# Sheet1.net
KiCad netlist of a schematic drawn in Altium Designer
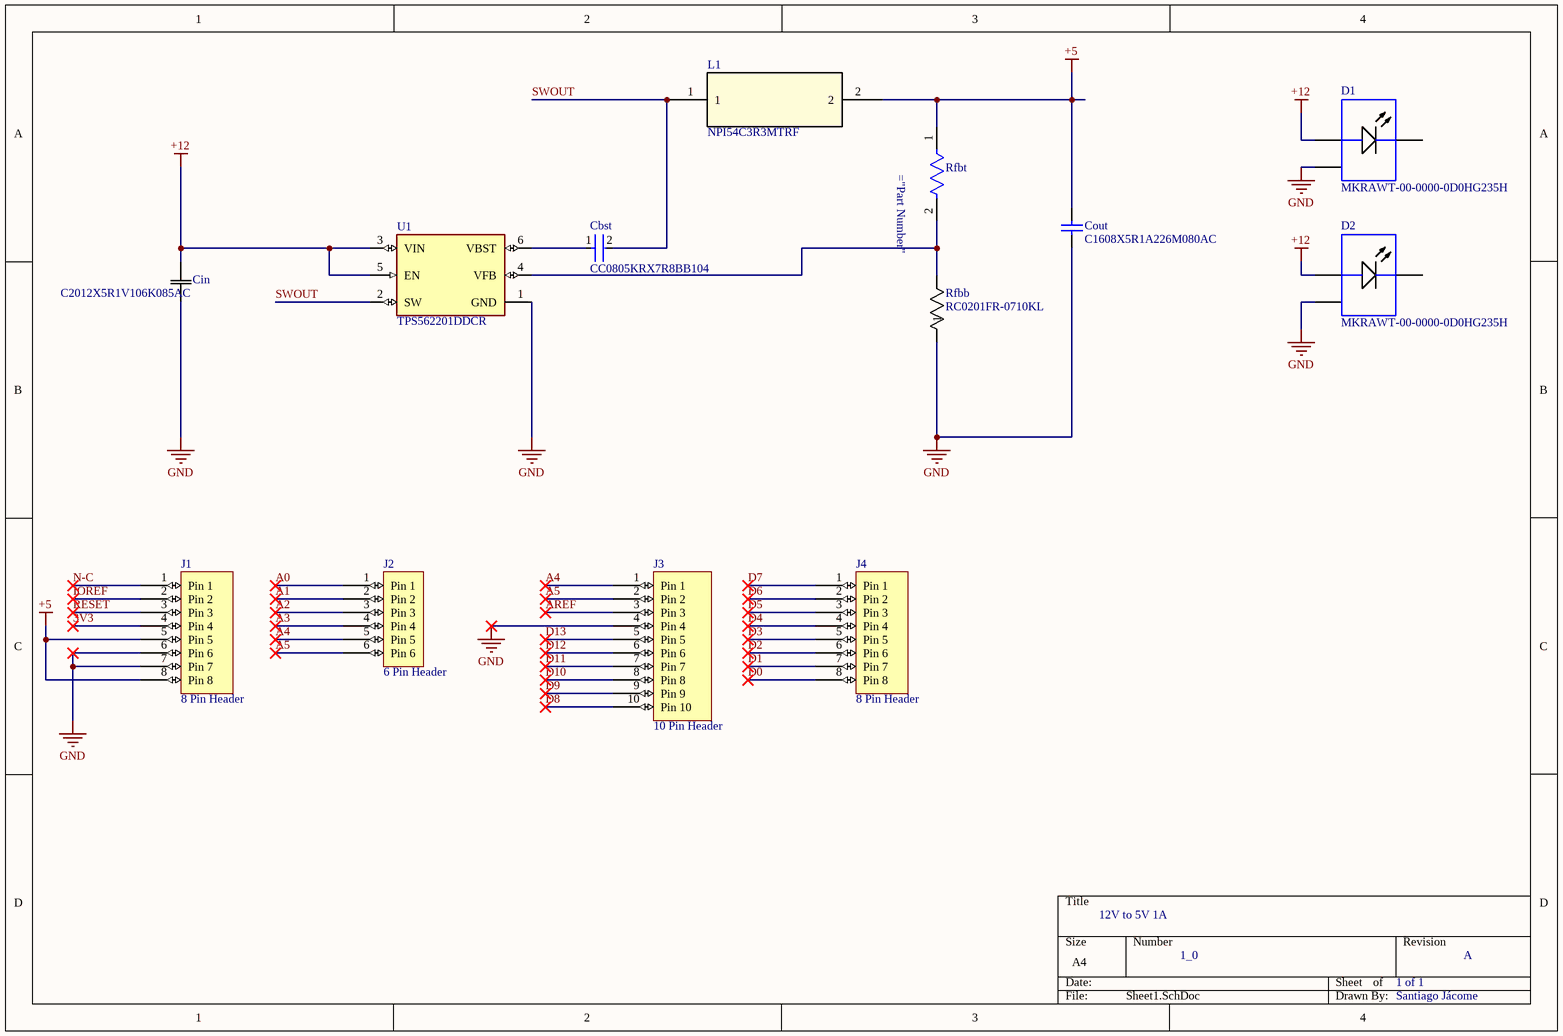
[diagram p0: Sheet1.SchDoc]

(export (version "E")
  (design (tool "Eeschema 10.0.6"))
  (components
    (comp (ref "Cbst")
      (value "CC0805KRX7R8BB104")
      (footprint "FP-CC0805-0_85-MFG")
      (description "CAP CER 0.1UF 25V X7R 0805")
      (fields (field (name "TOLERANCE") "0.1") (field (name "MANUFACTURER") "Yageo"))
      (libsource (lib "Altium Content Vault") (part "11868f565c42a9108669ba33697ecf6"))
    )
    (comp (ref "Cin")
      (value "C2012X5R1V106K085AC")
      (footprint "C2012X5R1V106K085AC:CAP_2012_TDK-M")
      (description "10uf")
      (libsource (lib "C2012X5R1V106K085AC") (part "C2012X5R1V106K085AC"))
    )
    (comp (ref "Cout")
      (value "C1608X5R1A226M080AC")
      (footprint "CAPC1608X100X20ML10")
      (description "Chip Capacitor, 22 uF, +/- 20%, 10 V, -55 to 85 degC, 0603 (1608 Metric), RoHS, Tape and Reel")
      (fields (field (name "MANUFACTURER") "TDK") (field (name "TOLERANCE") "±20%"))
      (libsource (lib "Altium Content Vault") (part "CAP-NP-2"))
    )
    (comp (ref "D1")
      (value "MKRAWT-00-0000-0D0HG235H")
      (footprint "CREE-MK-R-2_V")
      (description "LED, White, 12 V, 2-Pin SMD, RoHS, Tape and Reel")
      (libsource (lib "Altium Content Vault") (part "LED_WHITE-3"))
    )
    (comp (ref "D2")
      (value "MKRAWT-00-0000-0D0HG235H")
      (footprint "CREE-MK-R-2_V")
      (description "LED, White, 12 V, 2-Pin SMD, RoHS, Tape and Reel")
      (libsource (lib "Altium Content Vault") (part "LED_WHITE-3"))
    )
    (comp (ref "J1")
      (value "8 Pin Header")
      (footprint "8 Pin Header-Footprint-1")
      (description "Arduino 8 Pin Header: 30 mils hole diameter, 60 mils pad diameter, 100 mils pin-to-pin")
      (libsource (lib "Altium Certification") (part "8 Pin Header-Symbol-1"))
    )
    (comp (ref "J2")
      (value "6 Pin Header")
      (footprint "6 Pin Header-Footprint-1")
      (description "Arduino 6 Pin Header: 30 mils hole diameter, 60 mils pad diameter, 100 mils pin-to-pin")
      (libsource (lib "Altium Certification") (part "6 Pin Header-Symbol-1"))
    )
    (comp (ref "J3")
      (value "10 Pin Header")
      (footprint "10 Pin Header-Footprint-1")
      (description "Arduino 10 Pin Header: 30 mils hole diameter, 60 mils pad diameter, 100 mils pin-to-pin")
      (libsource (lib "Altium Certification") (part "10 Pin Header-Symbol-1"))
    )
    (comp (ref "J4")
      (value "8 Pin Header")
      (footprint "8 Pin Header-Footprint-1")
      (description "Arduino 8 Pin Header: 30 mils hole diameter, 60 mils pad diameter, 100 mils pin-to-pin")
      (libsource (lib "Altium Certification") (part "8 Pin Header-Symbol-1"))
    )
    (comp (ref "L1")
      (value "NPI54C3R3MTRF")
      (footprint "NPI54C3R3MTRF_NIC")
      (description "No Description Available")
      (libsource (lib "NPI54C3R3MTRF") (part "NPI54C3R3MTRF"))
    )
    (comp (ref "Rfbb")
      (value "RC0201FR-0710KL")
      (footprint "YAG_R0201_YAG-L")
      (description "10k Ohms")
      (libsource (lib "RC0201FR-0710KL") (part "RC0201FR-0710KL"))
    )
    (comp (ref "Rfbt")
      (value "RC0201FR-0756K2L")
      (footprint "Yageo_RC0201_MFG")
      (description "56.2k Ohms")
      (libsource (lib "Res_Yageo_RC0201FR-0756K2L_eec") (part "RC0201FR-0756K2L"))
    )
    (comp (ref "U1")
      (value "TPS562201DDCR")
      (footprint "FP-DDC0006A-IPC_C")
      (description "IC REG BUCK ADJ 2A TSOT23-6")
      (libsource (lib "Altium Content Vault") (part "957e164956730ea4bf6293280af19fc"))
    )
  )
  (nets
    (net (code "1") (name "+5") (class "Default")
      (node (ref "Cout") (pin "2") (pinfunction "2_2") (pintype "passive"))
      (node (ref "J1") (pin "5") (pinfunction "Pin_5_5") (pintype "bidirectional"))
      (node (ref "J1") (pin "8") (pinfunction "Pin_8_8") (pintype "bidirectional"))
      (node (ref "L1") (pin "2") (pinfunction "2_2") (pintype "passive"))
      (node (ref "Rfbt") (pin "1") (pinfunction "1_1") (pintype "passive"))
    )
    (net (code "2") (name "+12") (class "Default")
      (node (ref "Cin") (pin "2") (pinfunction "2_2") (pintype "passive"))
      (node (ref "D1") (pin "1") (pinfunction "A_1") (pintype "passive"))
      (node (ref "D2") (pin "1") (pinfunction "A_1") (pintype "passive"))
      (node (ref "U1") (pin "3") (pinfunction "VIN_3") (pintype "bidirectional"))
      (node (ref "U1") (pin "5") (pinfunction "EN_5") (pintype "input"))
    )
    (net (code "3") (name "/3V3") (class "Default")
      (node (ref "J1") (pin "4") (pinfunction "Pin_4_4") (pintype "bidirectional+no_connect"))
    )
    (net (code "4") (name "/A0") (class "Default")
      (node (ref "J2") (pin "1") (pinfunction "Pin_1_1") (pintype "bidirectional+no_connect"))
    )
    (net (code "5") (name "/A1") (class "Default")
      (node (ref "J2") (pin "2") (pinfunction "Pin_2_2") (pintype "bidirectional+no_connect"))
    )
    (net (code "6") (name "/A2") (class "Default")
      (node (ref "J2") (pin "3") (pinfunction "Pin_3_3") (pintype "bidirectional+no_connect"))
    )
    (net (code "7") (name "/A3") (class "Default")
      (node (ref "J2") (pin "4") (pinfunction "Pin_4_4") (pintype "bidirectional+no_connect"))
    )
    (net (code "8") (name "/A4") (class "Default")
      (node (ref "J2") (pin "5") (pinfunction "Pin_5_5") (pintype "bidirectional"))
      (node (ref "J3") (pin "1") (pinfunction "Pin_1_1") (pintype "bidirectional"))
    )
    (net (code "9") (name "/A5") (class "Default")
      (node (ref "J2") (pin "6") (pinfunction "Pin_6_6") (pintype "bidirectional"))
      (node (ref "J3") (pin "2") (pinfunction "Pin_2_2") (pintype "bidirectional"))
    )
    (net (code "10") (name "/AREF") (class "Default")
      (node (ref "J3") (pin "3") (pinfunction "Pin_3_3") (pintype "bidirectional+no_connect"))
    )
    (net (code "11") (name "/D0") (class "Default")
      (node (ref "J4") (pin "8") (pinfunction "Pin_8_8") (pintype "bidirectional+no_connect"))
    )
    (net (code "12") (name "/D1") (class "Default")
      (node (ref "J4") (pin "7") (pinfunction "Pin_7_7") (pintype "bidirectional+no_connect"))
    )
    (net (code "13") (name "/D2") (class "Default")
      (node (ref "J4") (pin "6") (pinfunction "Pin_6_6") (pintype "bidirectional+no_connect"))
    )
    (net (code "14") (name "/D3") (class "Default")
      (node (ref "J4") (pin "5") (pinfunction "Pin_5_5") (pintype "bidirectional+no_connect"))
    )
    (net (code "15") (name "/D4") (class "Default")
      (node (ref "J4") (pin "4") (pinfunction "Pin_4_4") (pintype "bidirectional+no_connect"))
    )
    (net (code "16") (name "/D5") (class "Default")
      (node (ref "J4") (pin "3") (pinfunction "Pin_3_3") (pintype "bidirectional+no_connect"))
    )
    (net (code "17") (name "/D6") (class "Default")
      (node (ref "J4") (pin "2") (pinfunction "Pin_2_2") (pintype "bidirectional+no_connect"))
    )
    (net (code "18") (name "/D7") (class "Default")
      (node (ref "J4") (pin "1") (pinfunction "Pin_1_1") (pintype "bidirectional+no_connect"))
    )
    (net (code "19") (name "/D8") (class "Default")
      (node (ref "J3") (pin "10") (pinfunction "Pin_10_10") (pintype "bidirectional+no_connect"))
    )
    (net (code "20") (name "/D9") (class "Default")
      (node (ref "J3") (pin "9") (pinfunction "Pin_9_9") (pintype "bidirectional+no_connect"))
    )
    (net (code "21") (name "/D10") (class "Default")
      (node (ref "J3") (pin "8") (pinfunction "Pin_8_8") (pintype "bidirectional+no_connect"))
    )
    (net (code "22") (name "/D11") (class "Default")
      (node (ref "J3") (pin "7") (pinfunction "Pin_7_7") (pintype "bidirectional+no_connect"))
    )
    (net (code "23") (name "/D12") (class "Default")
      (node (ref "J3") (pin "6") (pinfunction "Pin_6_6") (pintype "bidirectional+no_connect"))
    )
    (net (code "24") (name "/D13") (class "Default")
      (node (ref "J3") (pin "5") (pinfunction "Pin_5_5") (pintype "bidirectional+no_connect"))
    )
    (net (code "25") (name "/IOREF") (class "Default")
      (node (ref "J1") (pin "2") (pinfunction "Pin_2_2") (pintype "bidirectional+no_connect"))
    )
    (net (code "26") (name "/N-C") (class "Default")
      (node (ref "J1") (pin "1") (pinfunction "Pin_1_1") (pintype "bidirectional+no_connect"))
    )
    (net (code "27") (name "/RESET") (class "Default")
      (node (ref "J1") (pin "3") (pinfunction "Pin_3_3") (pintype "bidirectional+no_connect"))
    )
    (net (code "28") (name "/SWOUT") (class "Default")
      (node (ref "Cbst") (pin "2") (pinfunction "2_2") (pintype "passive"))
      (node (ref "L1") (pin "1") (pinfunction "1_1") (pintype "passive"))
      (node (ref "U1") (pin "2") (pinfunction "SW_2") (pintype "bidirectional"))
    )
    (net (code "29") (name "GND") (class "Default")
      (node (ref "Cin") (pin "1") (pinfunction "1_1") (pintype "passive"))
      (node (ref "Cout") (pin "1") (pinfunction "1_1") (pintype "passive"))
      (node (ref "D1") (pin "3") (pinfunction "EP_3") (pintype "passive"))
      (node (ref "D2") (pin "3") (pinfunction "EP_3") (pintype "passive"))
      (node (ref "J1") (pin "6") (pinfunction "Pin_6_6") (pintype "bidirectional"))
      (node (ref "J1") (pin "7") (pinfunction "Pin_7_7") (pintype "bidirectional"))
      (node (ref "J3") (pin "4") (pinfunction "Pin_4_4") (pintype "bidirectional"))
      (node (ref "Rfbb") (pin "1") (pinfunction "1_1") (pintype "passive"))
      (node (ref "U1") (pin "1") (pinfunction "GND_1") (pintype "power_in"))
    )
    (net (code "30") (name "Net-(U1-VBST)") (class "Default")
      (node (ref "Cbst") (pin "1") (pinfunction "1_1") (pintype "passive"))
      (node (ref "U1") (pin "6") (pinfunction "VBST_6") (pintype "bidirectional"))
    )
    (net (code "31") (name "Net-(U1-VFB)") (class "Default")
      (node (ref "Rfbb") (pin "2") (pinfunction "2_2") (pintype "passive"))
      (node (ref "Rfbt") (pin "2") (pinfunction "2_2") (pintype "passive"))
      (node (ref "U1") (pin "4") (pinfunction "VFB_4") (pintype "bidirectional"))
    )
    (net (code "32") (name "unconnected-(D1-K-Pad2)") (class "Default")
      (node (ref "D1") (pin "2") (pinfunction "K_2") (pintype "passive"))
    )
    (net (code "33") (name "unconnected-(D2-K-Pad2)") (class "Default")
      (node (ref "D2") (pin "2") (pinfunction "K_2") (pintype "passive"))
    )
  )
)
